# rotary_enc.net
KiCad netlist of a schematic drawn in Altium Designer
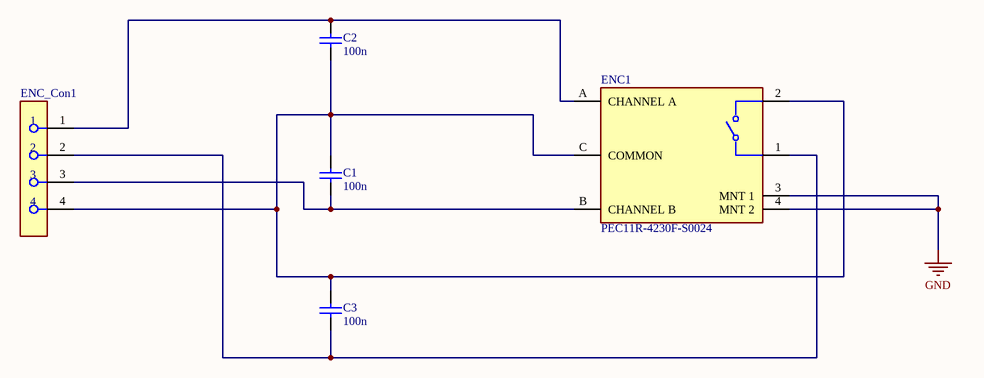
[diagram p0: rotary_enc.SchDoc]

(export (version "E")
  (design (tool "Eeschema 10.0.6"))
  (components
    (comp (ref "C1")
      (value "100n")
      (footprint "Capacitor_1206")
      (description "CAP, Ceramic, 0.1 uF, +/- 10%, 50 V, -55 to 125 degC, 1206 (3216 Metric), RoHS, Tape and Reel")
      (fields (field (name "MANUFACTURER") "Kemet"))
      (libsource (lib "library1") (part "Capacitor_1206"))
    )
    (comp (ref "C2")
      (value "100n")
      (footprint "Capacitor_1206")
      (description "CAP, Ceramic, 0.1 uF, +/- 10%, 50 V, -55 to 125 degC, 1206 (3216 Metric), RoHS, Tape and Reel")
      (fields (field (name "MANUFACTURER") "Kemet"))
      (libsource (lib "library1") (part "Capacitor_1206"))
    )
    (comp (ref "C3")
      (value "100n")
      (footprint "Capacitor_1206")
      (description "CAP, Ceramic, 0.1 uF, +/- 10%, 50 V, -55 to 125 degC, 1206 (3216 Metric), RoHS, Tape and Reel")
      (fields (field (name "MANUFACTURER") "Kemet"))
      (libsource (lib "library1") (part "Capacitor_1206"))
    )
    (comp (ref "ENC1")
      (value "PEC11R-4230F-S0024")
      (footprint "Rotary_Encoder_PEC11R-4230F-S0024")
      (description "ROTARY ENCODER MECHANICAL 24PPR")
      (libsource (lib "library1") (part "Rotary_Encoder_PEC11R-4230F-S0024"))
    )
    (comp (ref "ENC_Con1")
      (value "~")
      (footprint "Header-Female-JST_4pin")
      (libsource (lib "library1") (part "Header-Female-JST_4pin"))
    )
  )
  (nets
    (net (code "1") (name "GND") (class "Default")
      (node (ref "ENC1") (pin "3") (pinfunction "MNT_1_3") (pintype "passive"))
      (node (ref "ENC1") (pin "4") (pinfunction "MNT_2_4") (pintype "passive"))
    )
    (net (code "2") (name "Net-(C3-Pad1)") (class "Default")
      (node (ref "C3") (pin "1") (pinfunction "1_1") (pintype "passive"))
      (node (ref "ENC1") (pin "1") (pinfunction "1_1") (pintype "passive"))
      (node (ref "ENC_Con1") (pin "2") (pinfunction "2_2") (pintype "passive"))
    )
    (net (code "3") (name "Net-(ENC1-CHANNEL_A)") (class "Default")
      (node (ref "C2") (pin "2") (pinfunction "2_2") (pintype "passive"))
      (node (ref "ENC1") (pin "A") (pinfunction "CHANNEL_A_A") (pintype "passive"))
      (node (ref "ENC_Con1") (pin "1") (pinfunction "1_1") (pintype "passive"))
    )
    (net (code "4") (name "Net-(ENC1-CHANNEL_B)") (class "Default")
      (node (ref "C1") (pin "1") (pinfunction "1_1") (pintype "passive"))
      (node (ref "ENC1") (pin "B") (pinfunction "CHANNEL_B_B") (pintype "passive"))
      (node (ref "ENC_Con1") (pin "3") (pinfunction "3_3") (pintype "passive"))
    )
    (net (code "5") (name "Net-(ENC1-COMMON)") (class "Default")
      (node (ref "C1") (pin "2") (pinfunction "2_2") (pintype "passive"))
      (node (ref "C2") (pin "1") (pinfunction "1_1") (pintype "passive"))
      (node (ref "C3") (pin "2") (pinfunction "2_2") (pintype "passive"))
      (node (ref "ENC1") (pin "2") (pinfunction "2_2") (pintype "passive"))
      (node (ref "ENC1") (pin "C") (pinfunction "COMMON_C") (pintype "passive"))
      (node (ref "ENC_Con1") (pin "4") (pinfunction "4_4") (pintype "passive"))
    )
  )
)
